# ADJ_POS.net
KiCad netlist of a schematic drawn in EAGLE
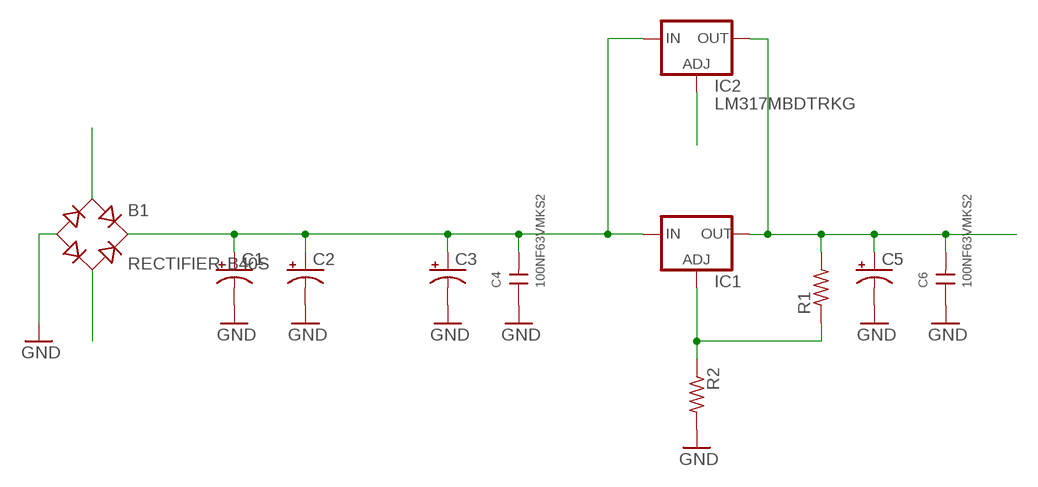
[diagram p0: schematic, sheet 1]

(export (version "E")
  (design (tool "Eeschema 10.0.6"))
  (components
    (comp (ref "B1")
      (value "RECTIFIER-B40S")
      (footprint "eagle-import:B40S")
      (libsource (lib "eagle-import") (part "RECTIFIER-B40S"))
    )
    (comp (ref "C1")
      (value "CPOL-USE7.5-16")
      (footprint "eagle-import:E7,5-16")
      (libsource (lib "eagle-import") (part "CPOL-USE7.5-16"))
    )
    (comp (ref "C2")
      (value "CPOL-USE7.5-16")
      (footprint "eagle-import:E7,5-16")
      (libsource (lib "eagle-import") (part "CPOL-USE7.5-16"))
    )
    (comp (ref "C3")
      (value "CPOL-USE2-5")
      (footprint "eagle-import:E2-5")
      (libsource (lib "eagle-import") (part "CPOL-USE2-5"))
    )
    (comp (ref "C4")
      (value "100NF63VMKS2")
      (footprint "eagle-import:2,5X6,5RM5,0")
      (libsource (lib "eagle-import") (part "100NF63VMKS2"))
    )
    (comp (ref "C5")
      (value "CPOL-USE2-5")
      (footprint "eagle-import:E2-5")
      (libsource (lib "eagle-import") (part "CPOL-USE2-5"))
    )
    (comp (ref "C6")
      (value "100NF63VMKS2")
      (footprint "eagle-import:2,5X6,5RM5,0")
      (libsource (lib "eagle-import") (part "100NF63VMKS2"))
    )
    (comp (ref "IC1")
      (value "LM317TS")
      (footprint "eagle-import:317TS")
      (libsource (lib "eagle-import") (part "LM317TS"))
    )
    (comp (ref "IC2")
      (value "LM317MBDTRKG")
      (footprint "eagle-import:DPACK")
      (libsource (lib "eagle-import") (part "LM317?MBDTRKG"))
    )
    (comp (ref "R1")
      (value "R-US_0309/12")
      (footprint "eagle-import:0309_12")
      (libsource (lib "eagle-import") (part "R-US_0309/12"))
    )
    (comp (ref "R2")
      (value "R-US_0309/12")
      (footprint "eagle-import:0309_12")
      (libsource (lib "eagle-import") (part "R-US_0309/12"))
    )
  )
  (nets
    (net (code "1") (name "/ADJ") (class "Default")
      (node (ref "IC1") (pin "1") (pinfunction "ADJ_1") (pintype "input"))
      (node (ref "IC2") (pin "1") (pinfunction "ADJ_1") (pintype "input"))
      (node (ref "R1") (pin "1") (pinfunction "1_1") (pintype "passive"))
      (node (ref "R2") (pin "1") (pinfunction "1_1") (pintype "passive"))
    )
    (net (code "2") (name "GND") (class "Default")
      (node (ref "B1") (pin "-") (pinfunction "-_-") (pintype "passive"))
      (node (ref "C1") (pin "-") (pinfunction "-_-") (pintype "passive"))
      (node (ref "C2") (pin "-") (pinfunction "-_-") (pintype "passive"))
      (node (ref "C3") (pin "-") (pinfunction "-_-") (pintype "passive"))
      (node (ref "C4") (pin "1") (pinfunction "1_1") (pintype "passive"))
      (node (ref "C5") (pin "-") (pinfunction "-_-") (pintype "passive"))
      (node (ref "C6") (pin "1") (pinfunction "1_1") (pintype "passive"))
      (node (ref "R2") (pin "2") (pinfunction "2_2") (pintype "passive"))
    )
    (net (code "3") (name "Net-(IC1-IN)") (class "Default")
      (node (ref "B1") (pin "+") (pinfunction "+_+") (pintype "passive"))
      (node (ref "C1") (pin "+") (pinfunction "+_+") (pintype "passive"))
      (node (ref "C2") (pin "+") (pinfunction "+_+") (pintype "passive"))
      (node (ref "C3") (pin "+") (pinfunction "+_+") (pintype "passive"))
      (node (ref "C4") (pin "2") (pinfunction "2_2") (pintype "passive"))
      (node (ref "IC1") (pin "3") (pinfunction "IN_3") (pintype "input"))
      (node (ref "IC2") (pin "3") (pinfunction "IN_3") (pintype "input"))
    )
    (net (code "4") (name "Net-(IC1-OUT)") (class "Default")
      (node (ref "C5") (pin "+") (pinfunction "+_+") (pintype "passive"))
      (node (ref "C6") (pin "2") (pinfunction "2_2") (pintype "passive"))
      (node (ref "IC1") (pin "2") (pinfunction "OUT_2") (pintype "passive"))
      (node (ref "IC2") (pin "4") (pinfunction "OUT_4") (pintype "passive"))
      (node (ref "R1") (pin "2") (pinfunction "2_2") (pintype "passive"))
    )
    (net (code "5") (name "unconnected-(B1-PadAC1)") (class "Default")
      (node (ref "B1") (pin "AC1") (pinfunction "AC1_AC1") (pintype "passive"))
    )
    (net (code "6") (name "unconnected-(B1-PadAC2)") (class "Default")
      (node (ref "B1") (pin "AC2") (pinfunction "AC2_AC2") (pintype "passive"))
    )
  )
)
